# audio2.net
KiCad netlist of a schematic drawn in EAGLE
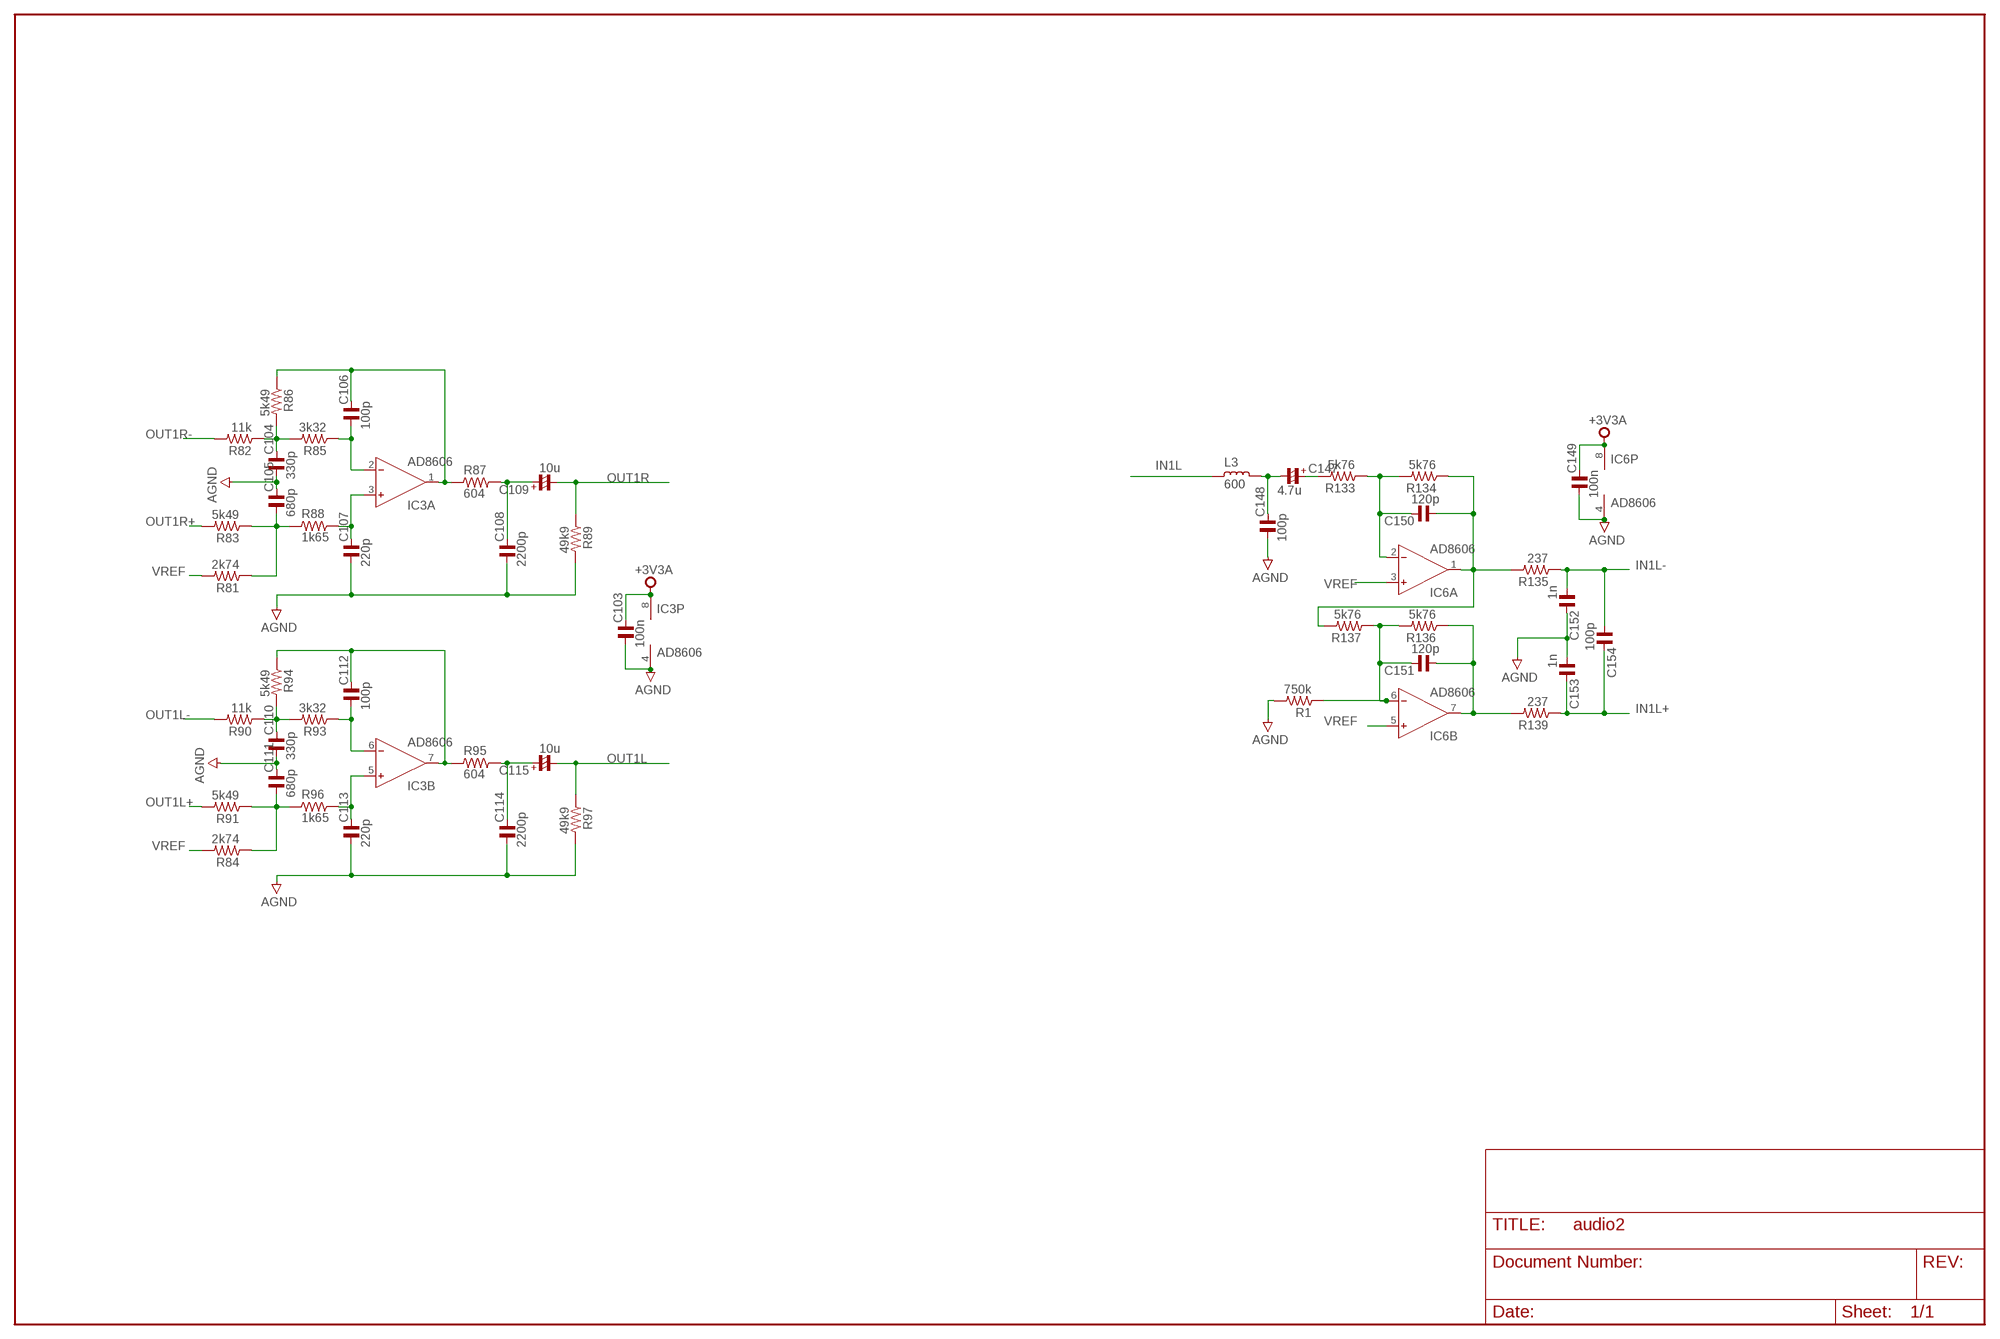
[diagram p0: schematic, sheet 1]

(export (version "E")
  (design (tool "Eeschema 10.0.6"))
  (components
    (comp (ref "C103")
      (value "100n")
      (footprint "eagle-import:C0603")
      (libsource (lib "eagle-import") (part "C_0603"))
    )
    (comp (ref "C104")
      (value "330p")
      (footprint "eagle-import:C0603")
      (libsource (lib "eagle-import") (part "C_0603"))
    )
    (comp (ref "C105")
      (value "680p")
      (footprint "eagle-import:C0603")
      (libsource (lib "eagle-import") (part "C_0603"))
    )
    (comp (ref "C106")
      (value "100p")
      (footprint "eagle-import:C0603")
      (libsource (lib "eagle-import") (part "C_0603"))
    )
    (comp (ref "C107")
      (value "220p")
      (footprint "eagle-import:C0603")
      (libsource (lib "eagle-import") (part "C_0603"))
    )
    (comp (ref "C108")
      (value "2200p")
      (footprint "eagle-import:C0603")
      (libsource (lib "eagle-import") (part "C_0603"))
    )
    (comp (ref "C109")
      (value "10u")
      (footprint "eagle-import:C1206_T")
      (libsource (lib "eagle-import") (part "CP_1206/T"))
    )
    (comp (ref "C110")
      (value "330p")
      (footprint "eagle-import:C0603")
      (libsource (lib "eagle-import") (part "C_0603"))
    )
    (comp (ref "C111")
      (value "680p")
      (footprint "eagle-import:C0603")
      (libsource (lib "eagle-import") (part "C_0603"))
    )
    (comp (ref "C112")
      (value "100p")
      (footprint "eagle-import:C0603")
      (libsource (lib "eagle-import") (part "C_0603"))
    )
    (comp (ref "C113")
      (value "220p")
      (footprint "eagle-import:C0603")
      (libsource (lib "eagle-import") (part "C_0603"))
    )
    (comp (ref "C114")
      (value "2200p")
      (footprint "eagle-import:C0603")
      (libsource (lib "eagle-import") (part "C_0603"))
    )
    (comp (ref "C115")
      (value "10u")
      (footprint "eagle-import:C1206_T")
      (libsource (lib "eagle-import") (part "CP_1206/T"))
    )
    (comp (ref "C147")
      (value "4.7u")
      (footprint "eagle-import:C1206_T")
      (libsource (lib "eagle-import") (part "CP_1206/T"))
    )
    (comp (ref "C148")
      (value "100p")
      (footprint "eagle-import:C0603")
      (libsource (lib "eagle-import") (part "C_0603"))
    )
    (comp (ref "C149")
      (value "100n")
      (footprint "eagle-import:C0603")
      (libsource (lib "eagle-import") (part "C_0603"))
    )
    (comp (ref "C150")
      (value "120p")
      (footprint "eagle-import:C0603")
      (libsource (lib "eagle-import") (part "C_0603"))
    )
    (comp (ref "C151")
      (value "120p")
      (footprint "eagle-import:C0603")
      (libsource (lib "eagle-import") (part "C_0603"))
    )
    (comp (ref "C152")
      (value "1n")
      (footprint "eagle-import:C0603")
      (libsource (lib "eagle-import") (part "C_0603"))
    )
    (comp (ref "C153")
      (value "1n")
      (footprint "eagle-import:C0603")
      (libsource (lib "eagle-import") (part "C_0603"))
    )
    (comp (ref "C154")
      (value "100p")
      (footprint "eagle-import:C0603")
      (libsource (lib "eagle-import") (part "C_0603"))
    )
    (comp (ref "IC3")
      (value "AD8606")
      (footprint "eagle-import:SO8")
      (fields (field (name "MPN") "AD8607ARMZ-R2"))
      (libsource (lib "eagle-import") (part "AD8607R"))
    )
    (comp (ref "IC6")
      (value "AD8606")
      (footprint "eagle-import:SO8")
      (fields (field (name "MPN") "AD8607ARMZ-R2"))
      (libsource (lib "eagle-import") (part "AD8607R"))
    )
    (comp (ref "L3")
      (value "600")
      (footprint "eagle-import:L1206")
      (libsource (lib "eagle-import") (part "L_1206"))
    )
    (comp (ref "R1")
      (value "750k")
      (footprint "eagle-import:R0603")
      (libsource (lib "eagle-import") (part "R_0603"))
    )
    (comp (ref "R81")
      (value "2k74")
      (footprint "eagle-import:R0603")
      (libsource (lib "eagle-import") (part "R_0603"))
    )
    (comp (ref "R82")
      (value "11k")
      (footprint "eagle-import:R0603")
      (libsource (lib "eagle-import") (part "R_0603"))
    )
    (comp (ref "R83")
      (value "5k49")
      (footprint "eagle-import:R0603")
      (libsource (lib "eagle-import") (part "R_0603"))
    )
    (comp (ref "R84")
      (value "2k74")
      (footprint "eagle-import:R0603")
      (libsource (lib "eagle-import") (part "R_0603"))
    )
    (comp (ref "R85")
      (value "3k32")
      (footprint "eagle-import:R0603")
      (libsource (lib "eagle-import") (part "R_0603"))
    )
    (comp (ref "R86")
      (value "5k49")
      (footprint "eagle-import:R0603")
      (libsource (lib "eagle-import") (part "R_0603"))
    )
    (comp (ref "R87")
      (value "604")
      (footprint "eagle-import:R0603")
      (libsource (lib "eagle-import") (part "R_0603"))
    )
    (comp (ref "R88")
      (value "1k65")
      (footprint "eagle-import:R0603")
      (libsource (lib "eagle-import") (part "R_0603"))
    )
    (comp (ref "R89")
      (value "49k9")
      (footprint "eagle-import:R0603")
      (libsource (lib "eagle-import") (part "R_0603"))
    )
    (comp (ref "R90")
      (value "11k")
      (footprint "eagle-import:R0603")
      (libsource (lib "eagle-import") (part "R_0603"))
    )
    (comp (ref "R91")
      (value "5k49")
      (footprint "eagle-import:R0603")
      (libsource (lib "eagle-import") (part "R_0603"))
    )
    (comp (ref "R93")
      (value "3k32")
      (footprint "eagle-import:R0603")
      (libsource (lib "eagle-import") (part "R_0603"))
    )
    (comp (ref "R94")
      (value "5k49")
      (footprint "eagle-import:R0603")
      (libsource (lib "eagle-import") (part "R_0603"))
    )
    (comp (ref "R95")
      (value "604")
      (footprint "eagle-import:R0603")
      (libsource (lib "eagle-import") (part "R_0603"))
    )
    (comp (ref "R96")
      (value "1k65")
      (footprint "eagle-import:R0603")
      (libsource (lib "eagle-import") (part "R_0603"))
    )
    (comp (ref "R97")
      (value "49k9")
      (footprint "eagle-import:R0603")
      (libsource (lib "eagle-import") (part "R_0603"))
    )
    (comp (ref "R133")
      (value "5k76")
      (footprint "eagle-import:R0603")
      (libsource (lib "eagle-import") (part "R_0603"))
    )
    (comp (ref "R134")
      (value "5k76")
      (footprint "eagle-import:R0603")
      (libsource (lib "eagle-import") (part "R_0603"))
    )
    (comp (ref "R135")
      (value "237")
      (footprint "eagle-import:R0603")
      (libsource (lib "eagle-import") (part "R_0603"))
    )
    (comp (ref "R136")
      (value "5k76")
      (footprint "eagle-import:R0603")
      (libsource (lib "eagle-import") (part "R_0603"))
    )
    (comp (ref "R137")
      (value "5k76")
      (footprint "eagle-import:R0603")
      (libsource (lib "eagle-import") (part "R_0603"))
    )
    (comp (ref "R139")
      (value "237")
      (footprint "eagle-import:R0603")
      (libsource (lib "eagle-import") (part "R_0603"))
    )
  )
  (nets
    (net (code "1") (name "+3V3A") (class "Default")
      (node (ref "C103") (pin "2") (pinfunction "2_2") (pintype "passive"))
      (node (ref "C149") (pin "2") (pinfunction "2_2") (pintype "passive"))
      (node (ref "IC3") (pin "8") (pinfunction "V+_8") (pintype "power_in"))
      (node (ref "IC6") (pin "8") (pinfunction "V+_8") (pintype "power_in"))
    )
    (net (code "2") (name "/IN1L") (class "Default")
      (node (ref "L3") (pin "2") (pinfunction "2_2") (pintype "passive"))
    )
    (net (code "3") (name "/IN1L+") (class "Default")
      (node (ref "C153") (pin "2") (pinfunction "2_2") (pintype "passive"))
      (node (ref "C154") (pin "2") (pinfunction "2_2") (pintype "passive"))
      (node (ref "R139") (pin "1") (pinfunction "1_1") (pintype "passive"))
    )
    (net (code "4") (name "/IN1L-") (class "Default")
      (node (ref "C152") (pin "1") (pinfunction "1_1") (pintype "passive"))
      (node (ref "C154") (pin "1") (pinfunction "1_1") (pintype "passive"))
      (node (ref "R135") (pin "1") (pinfunction "1_1") (pintype "passive"))
    )
    (net (code "5") (name "/OUT1L") (class "Default")
      (node (ref "C115") (pin "-") (pinfunction "-_-") (pintype "passive"))
      (node (ref "R97") (pin "1") (pinfunction "1_1") (pintype "passive"))
    )
    (net (code "6") (name "/OUT1L+") (class "Default")
      (node (ref "R91") (pin "2") (pinfunction "2_2") (pintype "passive"))
    )
    (net (code "7") (name "/OUT1L-") (class "Default")
      (node (ref "R90") (pin "2") (pinfunction "2_2") (pintype "passive"))
    )
    (net (code "8") (name "/OUT1R") (class "Default")
      (node (ref "C109") (pin "-") (pinfunction "-_-") (pintype "passive"))
      (node (ref "R89") (pin "1") (pinfunction "1_1") (pintype "passive"))
    )
    (net (code "9") (name "/OUT1R+") (class "Default")
      (node (ref "R83") (pin "2") (pinfunction "2_2") (pintype "passive"))
    )
    (net (code "10") (name "/OUT1R-") (class "Default")
      (node (ref "R82") (pin "2") (pinfunction "2_2") (pintype "passive"))
    )
    (net (code "11") (name "/VREF") (class "Default")
      (node (ref "IC6") (pin "3") (pinfunction "IN+_3") (pintype "input"))
      (node (ref "IC6") (pin "5") (pinfunction "IN+_5") (pintype "input"))
      (node (ref "R81") (pin "2") (pinfunction "2_2") (pintype "passive"))
      (node (ref "R84") (pin "2") (pinfunction "2_2") (pintype "passive"))
    )
    (net (code "12") (name "AGND") (class "Default")
      (node (ref "C103") (pin "1") (pinfunction "1_1") (pintype "passive"))
      (node (ref "C104") (pin "1") (pinfunction "1_1") (pintype "passive"))
      (node (ref "C105") (pin "2") (pinfunction "2_2") (pintype "passive"))
      (node (ref "C107") (pin "1") (pinfunction "1_1") (pintype "passive"))
      (node (ref "C108") (pin "1") (pinfunction "1_1") (pintype "passive"))
      (node (ref "C110") (pin "1") (pinfunction "1_1") (pintype "passive"))
      (node (ref "C111") (pin "2") (pinfunction "2_2") (pintype "passive"))
      (node (ref "C113") (pin "1") (pinfunction "1_1") (pintype "passive"))
      (node (ref "C114") (pin "1") (pinfunction "1_1") (pintype "passive"))
      (node (ref "C148") (pin "1") (pinfunction "1_1") (pintype "passive"))
      (node (ref "C149") (pin "1") (pinfunction "1_1") (pintype "passive"))
      (node (ref "C152") (pin "2") (pinfunction "2_2") (pintype "passive"))
      (node (ref "C153") (pin "1") (pinfunction "1_1") (pintype "passive"))
      (node (ref "IC3") (pin "4") (pinfunction "V-_4") (pintype "power_in"))
      (node (ref "IC6") (pin "4") (pinfunction "V-_4") (pintype "power_in"))
      (node (ref "R1") (pin "2") (pinfunction "2_2") (pintype "passive"))
      (node (ref "R89") (pin "2") (pinfunction "2_2") (pintype "passive"))
      (node (ref "R97") (pin "2") (pinfunction "2_2") (pintype "passive"))
    )
    (net (code "13") (name "Net-(C104-Pad2)") (class "Default")
      (node (ref "C104") (pin "2") (pinfunction "2_2") (pintype "passive"))
      (node (ref "R82") (pin "1") (pinfunction "1_1") (pintype "passive"))
      (node (ref "R85") (pin "2") (pinfunction "2_2") (pintype "passive"))
      (node (ref "R86") (pin "2") (pinfunction "2_2") (pintype "passive"))
    )
    (net (code "14") (name "Net-(C105-Pad1)") (class "Default")
      (node (ref "C105") (pin "1") (pinfunction "1_1") (pintype "passive"))
      (node (ref "R81") (pin "1") (pinfunction "1_1") (pintype "passive"))
      (node (ref "R83") (pin "1") (pinfunction "1_1") (pintype "passive"))
      (node (ref "R88") (pin "1") (pinfunction "1_1") (pintype "passive"))
    )
    (net (code "15") (name "Net-(C108-Pad2)") (class "Default")
      (node (ref "C108") (pin "2") (pinfunction "2_2") (pintype "passive"))
      (node (ref "C109") (pin "+") (pinfunction "+_+") (pintype "passive"))
      (node (ref "R87") (pin "2") (pinfunction "2_2") (pintype "passive"))
    )
    (net (code "16") (name "Net-(C110-Pad2)") (class "Default")
      (node (ref "C110") (pin "2") (pinfunction "2_2") (pintype "passive"))
      (node (ref "R90") (pin "1") (pinfunction "1_1") (pintype "passive"))
      (node (ref "R93") (pin "2") (pinfunction "2_2") (pintype "passive"))
      (node (ref "R94") (pin "2") (pinfunction "2_2") (pintype "passive"))
    )
    (net (code "17") (name "Net-(C111-Pad1)") (class "Default")
      (node (ref "C111") (pin "1") (pinfunction "1_1") (pintype "passive"))
      (node (ref "R84") (pin "1") (pinfunction "1_1") (pintype "passive"))
      (node (ref "R91") (pin "1") (pinfunction "1_1") (pintype "passive"))
      (node (ref "R96") (pin "1") (pinfunction "1_1") (pintype "passive"))
    )
    (net (code "18") (name "Net-(C114-Pad2)") (class "Default")
      (node (ref "C114") (pin "2") (pinfunction "2_2") (pintype "passive"))
      (node (ref "C115") (pin "+") (pinfunction "+_+") (pintype "passive"))
      (node (ref "R95") (pin "2") (pinfunction "2_2") (pintype "passive"))
    )
    (net (code "19") (name "Net-(C147-Pad+)") (class "Default")
      (node (ref "C147") (pin "+") (pinfunction "+_+") (pintype "passive"))
      (node (ref "R133") (pin "2") (pinfunction "2_2") (pintype "passive"))
    )
    (net (code "20") (name "Net-(C147-Pad-)") (class "Default")
      (node (ref "C147") (pin "-") (pinfunction "-_-") (pintype "passive"))
      (node (ref "C148") (pin "2") (pinfunction "2_2") (pintype "passive"))
      (node (ref "L3") (pin "1") (pinfunction "1_1") (pintype "passive"))
    )
    (net (code "21") (name "Net-(IC3A-IN+)") (class "Default")
      (node (ref "C107") (pin "2") (pinfunction "2_2") (pintype "passive"))
      (node (ref "IC3") (pin "3") (pinfunction "IN+_3") (pintype "input"))
      (node (ref "R88") (pin "2") (pinfunction "2_2") (pintype "passive"))
    )
    (net (code "22") (name "Net-(IC3A-IN-)") (class "Default")
      (node (ref "C106") (pin "1") (pinfunction "1_1") (pintype "passive"))
      (node (ref "IC3") (pin "2") (pinfunction "IN-_2") (pintype "input"))
      (node (ref "R85") (pin "1") (pinfunction "1_1") (pintype "passive"))
    )
    (net (code "23") (name "Net-(IC3A-OUT)") (class "Default")
      (node (ref "C106") (pin "2") (pinfunction "2_2") (pintype "passive"))
      (node (ref "IC3") (pin "1") (pinfunction "OUT_1") (pintype "output"))
      (node (ref "R86") (pin "1") (pinfunction "1_1") (pintype "passive"))
      (node (ref "R87") (pin "1") (pinfunction "1_1") (pintype "passive"))
    )
    (net (code "24") (name "Net-(IC3B-IN+)") (class "Default")
      (node (ref "C113") (pin "2") (pinfunction "2_2") (pintype "passive"))
      (node (ref "IC3") (pin "5") (pinfunction "IN+_5") (pintype "input"))
      (node (ref "R96") (pin "2") (pinfunction "2_2") (pintype "passive"))
    )
    (net (code "25") (name "Net-(IC3B-IN-)") (class "Default")
      (node (ref "C112") (pin "1") (pinfunction "1_1") (pintype "passive"))
      (node (ref "IC3") (pin "6") (pinfunction "IN-_6") (pintype "input"))
      (node (ref "R93") (pin "1") (pinfunction "1_1") (pintype "passive"))
    )
    (net (code "26") (name "Net-(IC3B-OUT)") (class "Default")
      (node (ref "C112") (pin "2") (pinfunction "2_2") (pintype "passive"))
      (node (ref "IC3") (pin "7") (pinfunction "OUT_7") (pintype "output"))
      (node (ref "R94") (pin "1") (pinfunction "1_1") (pintype "passive"))
      (node (ref "R95") (pin "1") (pinfunction "1_1") (pintype "passive"))
    )
    (net (code "27") (name "Net-(IC6A-IN-)") (class "Default")
      (node (ref "C150") (pin "2") (pinfunction "2_2") (pintype "passive"))
      (node (ref "IC6") (pin "2") (pinfunction "IN-_2") (pintype "input"))
      (node (ref "R133") (pin "1") (pinfunction "1_1") (pintype "passive"))
      (node (ref "R134") (pin "2") (pinfunction "2_2") (pintype "passive"))
    )
    (net (code "28") (name "Net-(IC6A-OUT)") (class "Default")
      (node (ref "C150") (pin "1") (pinfunction "1_1") (pintype "passive"))
      (node (ref "IC6") (pin "1") (pinfunction "OUT_1") (pintype "output"))
      (node (ref "R134") (pin "1") (pinfunction "1_1") (pintype "passive"))
      (node (ref "R135") (pin "2") (pinfunction "2_2") (pintype "passive"))
      (node (ref "R137") (pin "2") (pinfunction "2_2") (pintype "passive"))
    )
    (net (code "29") (name "Net-(IC6B-IN-)") (class "Default")
      (node (ref "C151") (pin "2") (pinfunction "2_2") (pintype "passive"))
      (node (ref "IC6") (pin "6") (pinfunction "IN-_6") (pintype "input"))
      (node (ref "R1") (pin "1") (pinfunction "1_1") (pintype "passive"))
      (node (ref "R136") (pin "2") (pinfunction "2_2") (pintype "passive"))
      (node (ref "R137") (pin "1") (pinfunction "1_1") (pintype "passive"))
    )
    (net (code "30") (name "Net-(IC6B-OUT)") (class "Default")
      (node (ref "C151") (pin "1") (pinfunction "1_1") (pintype "passive"))
      (node (ref "IC6") (pin "7") (pinfunction "OUT_7") (pintype "output"))
      (node (ref "R136") (pin "1") (pinfunction "1_1") (pintype "passive"))
      (node (ref "R139") (pin "2") (pinfunction "2_2") (pintype "passive"))
    )
  )
)
